# blimp_v2.net
KiCad netlist of a schematic drawn in EAGLE
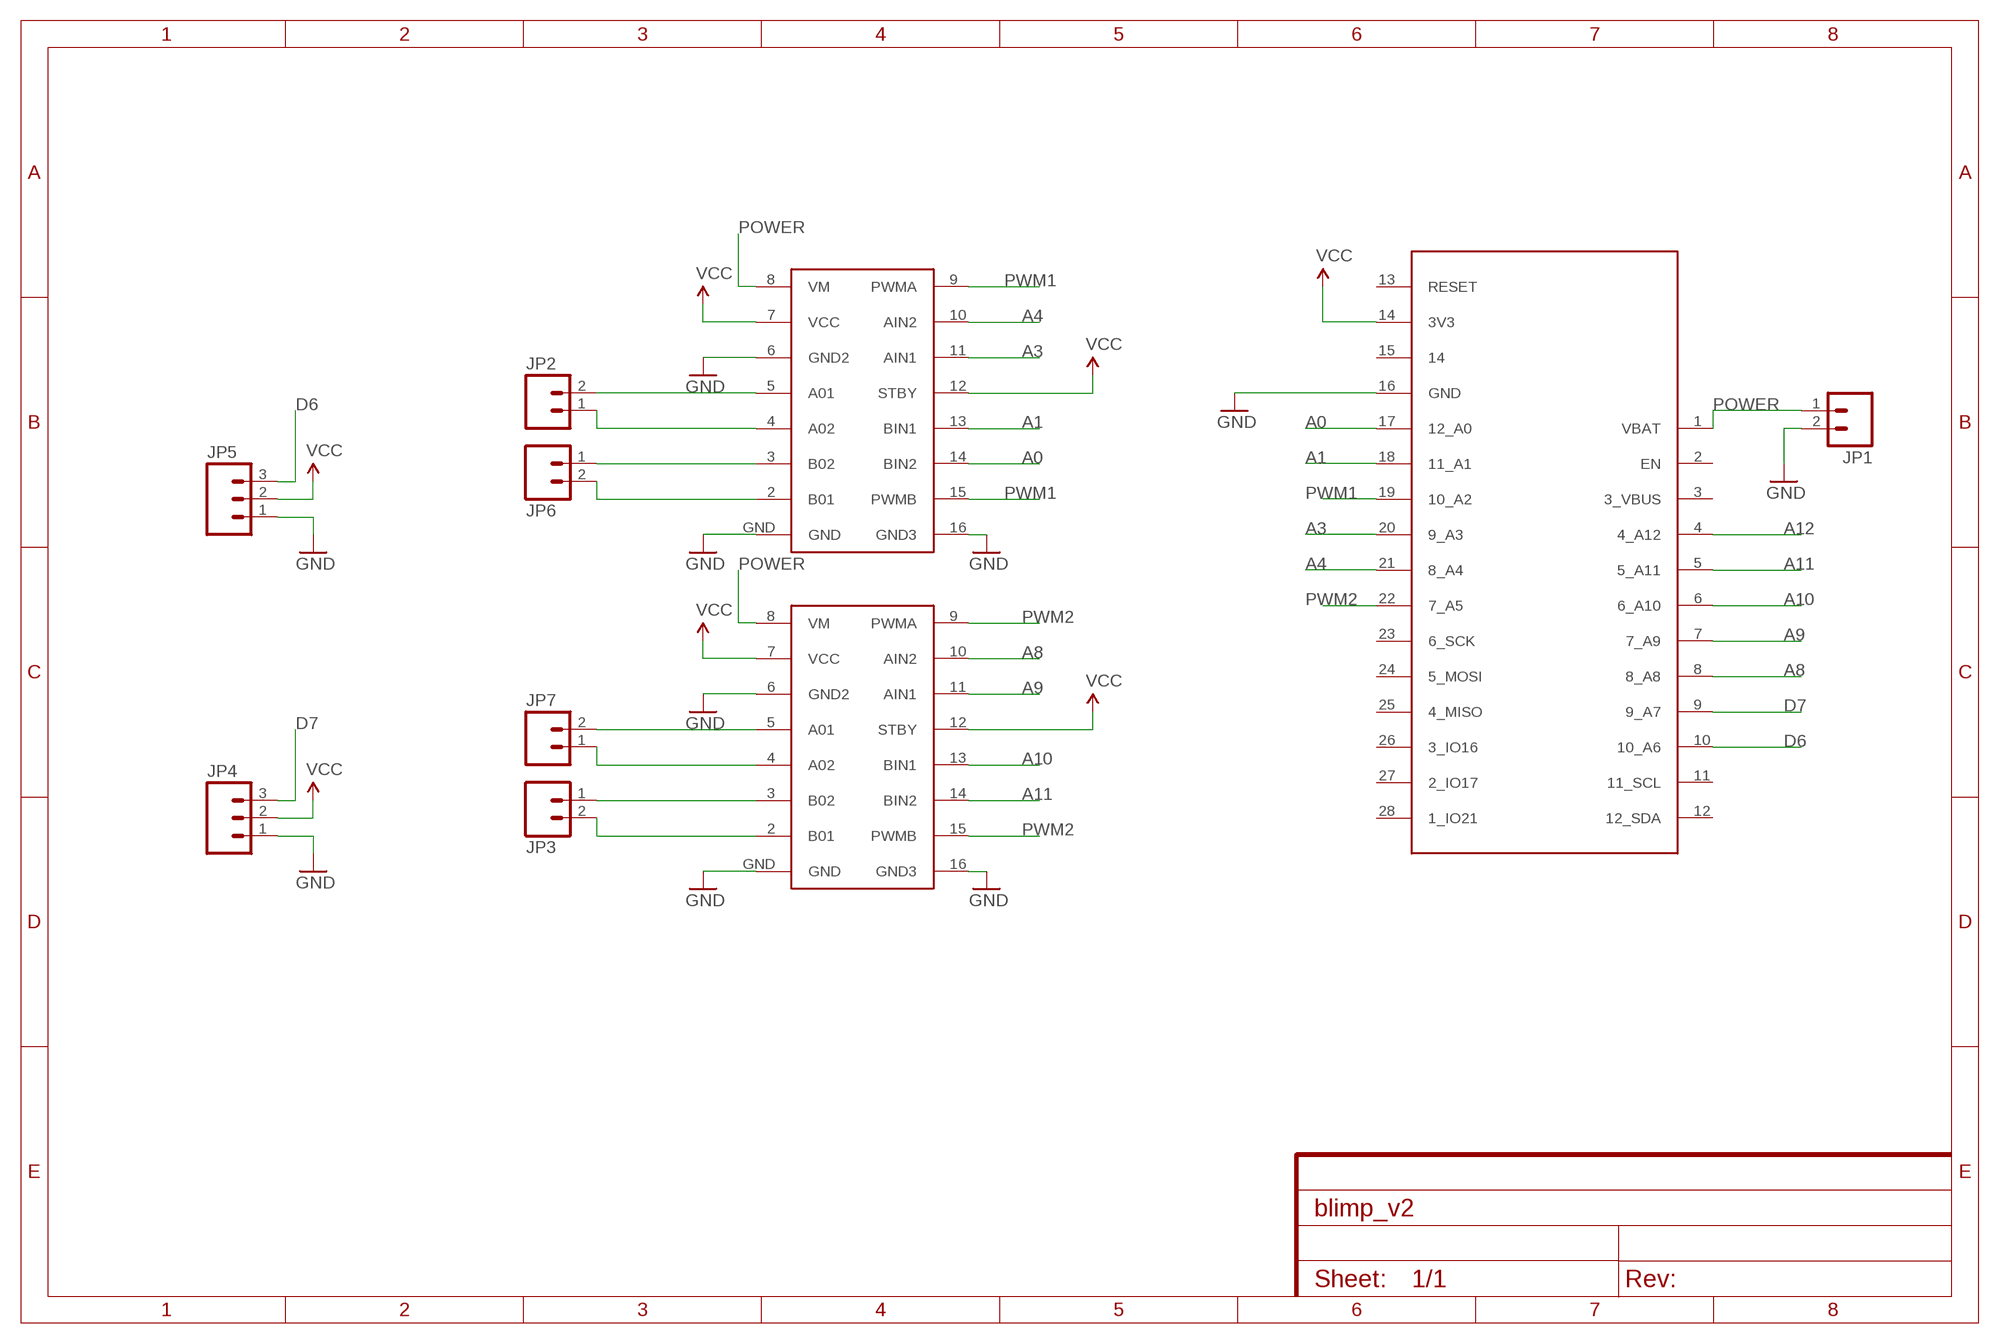
[diagram p0: schematic, sheet 1]

(export (version "E")
  (design (tool "Eeschema 10.0.6"))
  (components
    (comp (ref "JP1")
      (value "M02-JST-2MM-SMT")
      (footprint "eagle-import:JST-2-SMD")
      (libsource (lib "eagle-import") (part "M02-JST-2MM-SMT"))
    )
    (comp (ref "JP2")
      (value "M02PTH")
      (footprint "eagle-import:1X02")
      (libsource (lib "eagle-import") (part "M02PTH"))
    )
    (comp (ref "JP3")
      (value "M02PTH")
      (footprint "eagle-import:1X02")
      (libsource (lib "eagle-import") (part "M02PTH"))
    )
    (comp (ref "JP4")
      (value "M03PTH")
      (footprint "eagle-import:1X03")
      (libsource (lib "eagle-import") (part "M03PTH"))
    )
    (comp (ref "JP5")
      (value "M03PTH")
      (footprint "eagle-import:1X03")
      (libsource (lib "eagle-import") (part "M03PTH"))
    )
    (comp (ref "JP6")
      (value "M02PTH")
      (footprint "eagle-import:1X02")
      (libsource (lib "eagle-import") (part "M02PTH"))
    )
    (comp (ref "JP7")
      (value "M02PTH")
      (footprint "eagle-import:1X02")
      (libsource (lib "eagle-import") (part "M02PTH"))
    )
    (comp (ref "U$1")
      (value "ESP32")
      (footprint "eagle-import:ESP32")
      (libsource (lib "eagle-import") (part "ESP32"))
    )
    (comp (ref "U$2")
      (value "TB6612")
      (footprint "eagle-import:TB6612")
      (libsource (lib "eagle-import") (part "TB6612"))
    )
    (comp (ref "U$4")
      (value "TB6612")
      (footprint "eagle-import:TB6612")
      (libsource (lib "eagle-import") (part "TB6612"))
    )
  )
  (nets
    (net (code "1") (name "/A0") (class "Default")
      (node (ref "U$1") (pin "17") (pinfunction "12_A0_17") (pintype "bidirectional"))
      (node (ref "U$4") (pin "14") (pinfunction "BIN2_14") (pintype "bidirectional"))
    )
    (net (code "2") (name "/A1") (class "Default")
      (node (ref "U$1") (pin "18") (pinfunction "11_A1_18") (pintype "bidirectional"))
      (node (ref "U$4") (pin "13") (pinfunction "BIN1_13") (pintype "bidirectional"))
    )
    (net (code "3") (name "/A3") (class "Default")
      (node (ref "U$1") (pin "20") (pinfunction "9_A3_20") (pintype "bidirectional"))
      (node (ref "U$4") (pin "11") (pinfunction "AIN1_11") (pintype "bidirectional"))
    )
    (net (code "4") (name "/A4") (class "Default")
      (node (ref "U$1") (pin "21") (pinfunction "8_A4_21") (pintype "bidirectional"))
      (node (ref "U$4") (pin "10") (pinfunction "AIN2_10") (pintype "bidirectional"))
    )
    (net (code "5") (name "/A8") (class "Default")
      (node (ref "U$1") (pin "8") (pinfunction "8_A8_8") (pintype "bidirectional"))
      (node (ref "U$2") (pin "10") (pinfunction "AIN2_10") (pintype "bidirectional"))
    )
    (net (code "6") (name "/A9") (class "Default")
      (node (ref "U$1") (pin "7") (pinfunction "7_A9_7") (pintype "bidirectional"))
      (node (ref "U$2") (pin "11") (pinfunction "AIN1_11") (pintype "bidirectional"))
    )
    (net (code "7") (name "/A10") (class "Default")
      (node (ref "U$1") (pin "6") (pinfunction "6_A10_6") (pintype "bidirectional"))
      (node (ref "U$2") (pin "13") (pinfunction "BIN1_13") (pintype "bidirectional"))
    )
    (net (code "8") (name "/A11") (class "Default")
      (node (ref "U$1") (pin "5") (pinfunction "5_A11_5") (pintype "bidirectional"))
      (node (ref "U$2") (pin "14") (pinfunction "BIN2_14") (pintype "bidirectional"))
    )
    (net (code "9") (name "/A12") (class "Default")
      (node (ref "U$1") (pin "4") (pinfunction "4_A12_4") (pintype "bidirectional"))
    )
    (net (code "10") (name "/D6") (class "Default")
      (node (ref "JP5") (pin "3") (pinfunction "3_3") (pintype "passive"))
      (node (ref "U$1") (pin "10") (pinfunction "10_A6_10") (pintype "bidirectional"))
    )
    (net (code "11") (name "/D7") (class "Default")
      (node (ref "JP4") (pin "3") (pinfunction "3_3") (pintype "passive"))
      (node (ref "U$1") (pin "9") (pinfunction "9_A7_9") (pintype "bidirectional"))
    )
    (net (code "12") (name "/POWER") (class "Default")
      (node (ref "JP1") (pin "1") (pinfunction "1_1") (pintype "passive"))
      (node (ref "U$1") (pin "1") (pinfunction "VBAT_1") (pintype "bidirectional"))
      (node (ref "U$2") (pin "8") (pinfunction "VM_8") (pintype "bidirectional"))
      (node (ref "U$4") (pin "8") (pinfunction "VM_8") (pintype "bidirectional"))
    )
    (net (code "13") (name "/PWM1") (class "Default")
      (node (ref "U$1") (pin "19") (pinfunction "10_A2_19") (pintype "bidirectional"))
      (node (ref "U$4") (pin "15") (pinfunction "PWMB_15") (pintype "bidirectional"))
      (node (ref "U$4") (pin "9") (pinfunction "PWMA_9") (pintype "bidirectional"))
    )
    (net (code "14") (name "/PWM2") (class "Default")
      (node (ref "U$1") (pin "22") (pinfunction "7_A5_22") (pintype "bidirectional"))
      (node (ref "U$2") (pin "15") (pinfunction "PWMB_15") (pintype "bidirectional"))
      (node (ref "U$2") (pin "9") (pinfunction "PWMA_9") (pintype "bidirectional"))
    )
    (net (code "15") (name "GND") (class "Default")
      (node (ref "JP1") (pin "2") (pinfunction "2_2") (pintype "passive"))
      (node (ref "JP4") (pin "1") (pinfunction "1_1") (pintype "passive"))
      (node (ref "JP5") (pin "1") (pinfunction "1_1") (pintype "passive"))
      (node (ref "U$1") (pin "16") (pinfunction "GND_16") (pintype "bidirectional"))
      (node (ref "U$2") (pin "16") (pinfunction "GND3_16") (pintype "bidirectional"))
      (node (ref "U$2") (pin "6") (pinfunction "GND2_6") (pintype "bidirectional"))
      (node (ref "U$2") (pin "GND") (pinfunction "GND_GND") (pintype "bidirectional"))
      (node (ref "U$4") (pin "16") (pinfunction "GND3_16") (pintype "bidirectional"))
      (node (ref "U$4") (pin "6") (pinfunction "GND2_6") (pintype "bidirectional"))
      (node (ref "U$4") (pin "GND") (pinfunction "GND_GND") (pintype "bidirectional"))
    )
    (net (code "16") (name "Net-(U$2-A01)") (class "Default")
      (node (ref "JP7") (pin "2") (pinfunction "2_2") (pintype "passive"))
      (node (ref "U$2") (pin "5") (pinfunction "A01_5") (pintype "bidirectional"))
    )
    (net (code "17") (name "Net-(U$2-A02)") (class "Default")
      (node (ref "JP7") (pin "1") (pinfunction "1_1") (pintype "passive"))
      (node (ref "U$2") (pin "4") (pinfunction "A02_4") (pintype "bidirectional"))
    )
    (net (code "18") (name "Net-(U$2-B01)") (class "Default")
      (node (ref "JP3") (pin "2") (pinfunction "2_2") (pintype "passive"))
      (node (ref "U$2") (pin "2") (pinfunction "B01_2") (pintype "bidirectional"))
    )
    (net (code "19") (name "Net-(U$2-B02)") (class "Default")
      (node (ref "JP3") (pin "1") (pinfunction "1_1") (pintype "passive"))
      (node (ref "U$2") (pin "3") (pinfunction "B02_3") (pintype "bidirectional"))
    )
    (net (code "20") (name "Net-(U$4-A01)") (class "Default")
      (node (ref "JP2") (pin "2") (pinfunction "2_2") (pintype "passive"))
      (node (ref "U$4") (pin "5") (pinfunction "A01_5") (pintype "bidirectional"))
    )
    (net (code "21") (name "Net-(U$4-A02)") (class "Default")
      (node (ref "JP2") (pin "1") (pinfunction "1_1") (pintype "passive"))
      (node (ref "U$4") (pin "4") (pinfunction "A02_4") (pintype "bidirectional"))
    )
    (net (code "22") (name "Net-(U$4-B01)") (class "Default")
      (node (ref "JP6") (pin "2") (pinfunction "2_2") (pintype "passive"))
      (node (ref "U$4") (pin "2") (pinfunction "B01_2") (pintype "bidirectional"))
    )
    (net (code "23") (name "Net-(U$4-B02)") (class "Default")
      (node (ref "JP6") (pin "1") (pinfunction "1_1") (pintype "passive"))
      (node (ref "U$4") (pin "3") (pinfunction "B02_3") (pintype "bidirectional"))
    )
    (net (code "24") (name "VCC") (class "Default")
      (node (ref "JP4") (pin "2") (pinfunction "2_2") (pintype "passive"))
      (node (ref "JP5") (pin "2") (pinfunction "2_2") (pintype "passive"))
      (node (ref "U$1") (pin "14") (pinfunction "3V3_14") (pintype "bidirectional"))
      (node (ref "U$2") (pin "12") (pinfunction "STBY_12") (pintype "bidirectional"))
      (node (ref "U$2") (pin "7") (pinfunction "VCC_7") (pintype "bidirectional"))
      (node (ref "U$4") (pin "12") (pinfunction "STBY_12") (pintype "bidirectional"))
      (node (ref "U$4") (pin "7") (pinfunction "VCC_7") (pintype "bidirectional"))
    )
    (net (code "25") (name "unconnected-(U$1-1_IO21-Pad28)") (class "Default")
      (node (ref "U$1") (pin "28") (pinfunction "1_IO21_28") (pintype "bidirectional"))
    )
    (net (code "26") (name "unconnected-(U$1-2_IO17-Pad27)") (class "Default")
      (node (ref "U$1") (pin "27") (pinfunction "2_IO17_27") (pintype "bidirectional"))
    )
    (net (code "27") (name "unconnected-(U$1-3_IO16-Pad26)") (class "Default")
      (node (ref "U$1") (pin "26") (pinfunction "3_IO16_26") (pintype "bidirectional"))
    )
    (net (code "28") (name "unconnected-(U$1-3_VBUS-Pad3)") (class "Default")
      (node (ref "U$1") (pin "3") (pinfunction "3_VBUS_3") (pintype "bidirectional"))
    )
    (net (code "29") (name "unconnected-(U$1-4_MISO-Pad25)") (class "Default")
      (node (ref "U$1") (pin "25") (pinfunction "4_MISO_25") (pintype "bidirectional"))
    )
    (net (code "30") (name "unconnected-(U$1-5_MOSI-Pad24)") (class "Default")
      (node (ref "U$1") (pin "24") (pinfunction "5_MOSI_24") (pintype "bidirectional"))
    )
    (net (code "31") (name "unconnected-(U$1-6_SCK-Pad23)") (class "Default")
      (node (ref "U$1") (pin "23") (pinfunction "6_SCK_23") (pintype "bidirectional"))
    )
    (net (code "32") (name "unconnected-(U$1-11_SCL-Pad11)") (class "Default")
      (node (ref "U$1") (pin "11") (pinfunction "11_SCL_11") (pintype "bidirectional"))
    )
    (net (code "33") (name "unconnected-(U$1-12_SDA-Pad12)") (class "Default")
      (node (ref "U$1") (pin "12") (pinfunction "12_SDA_12") (pintype "bidirectional"))
    )
    (net (code "34") (name "unconnected-(U$1-14-Pad15)") (class "Default")
      (node (ref "U$1") (pin "15") (pinfunction "14_15") (pintype "bidirectional"))
    )
    (net (code "35") (name "unconnected-(U$1-EN-Pad2)") (class "Default")
      (node (ref "U$1") (pin "2") (pinfunction "EN_2") (pintype "bidirectional"))
    )
    (net (code "36") (name "unconnected-(U$1-RESET-Pad13)") (class "Default")
      (node (ref "U$1") (pin "13") (pinfunction "RESET_13") (pintype "bidirectional"))
    )
  )
)
